# ps.net
KiCad netlist of a schematic drawn in Altium Designer
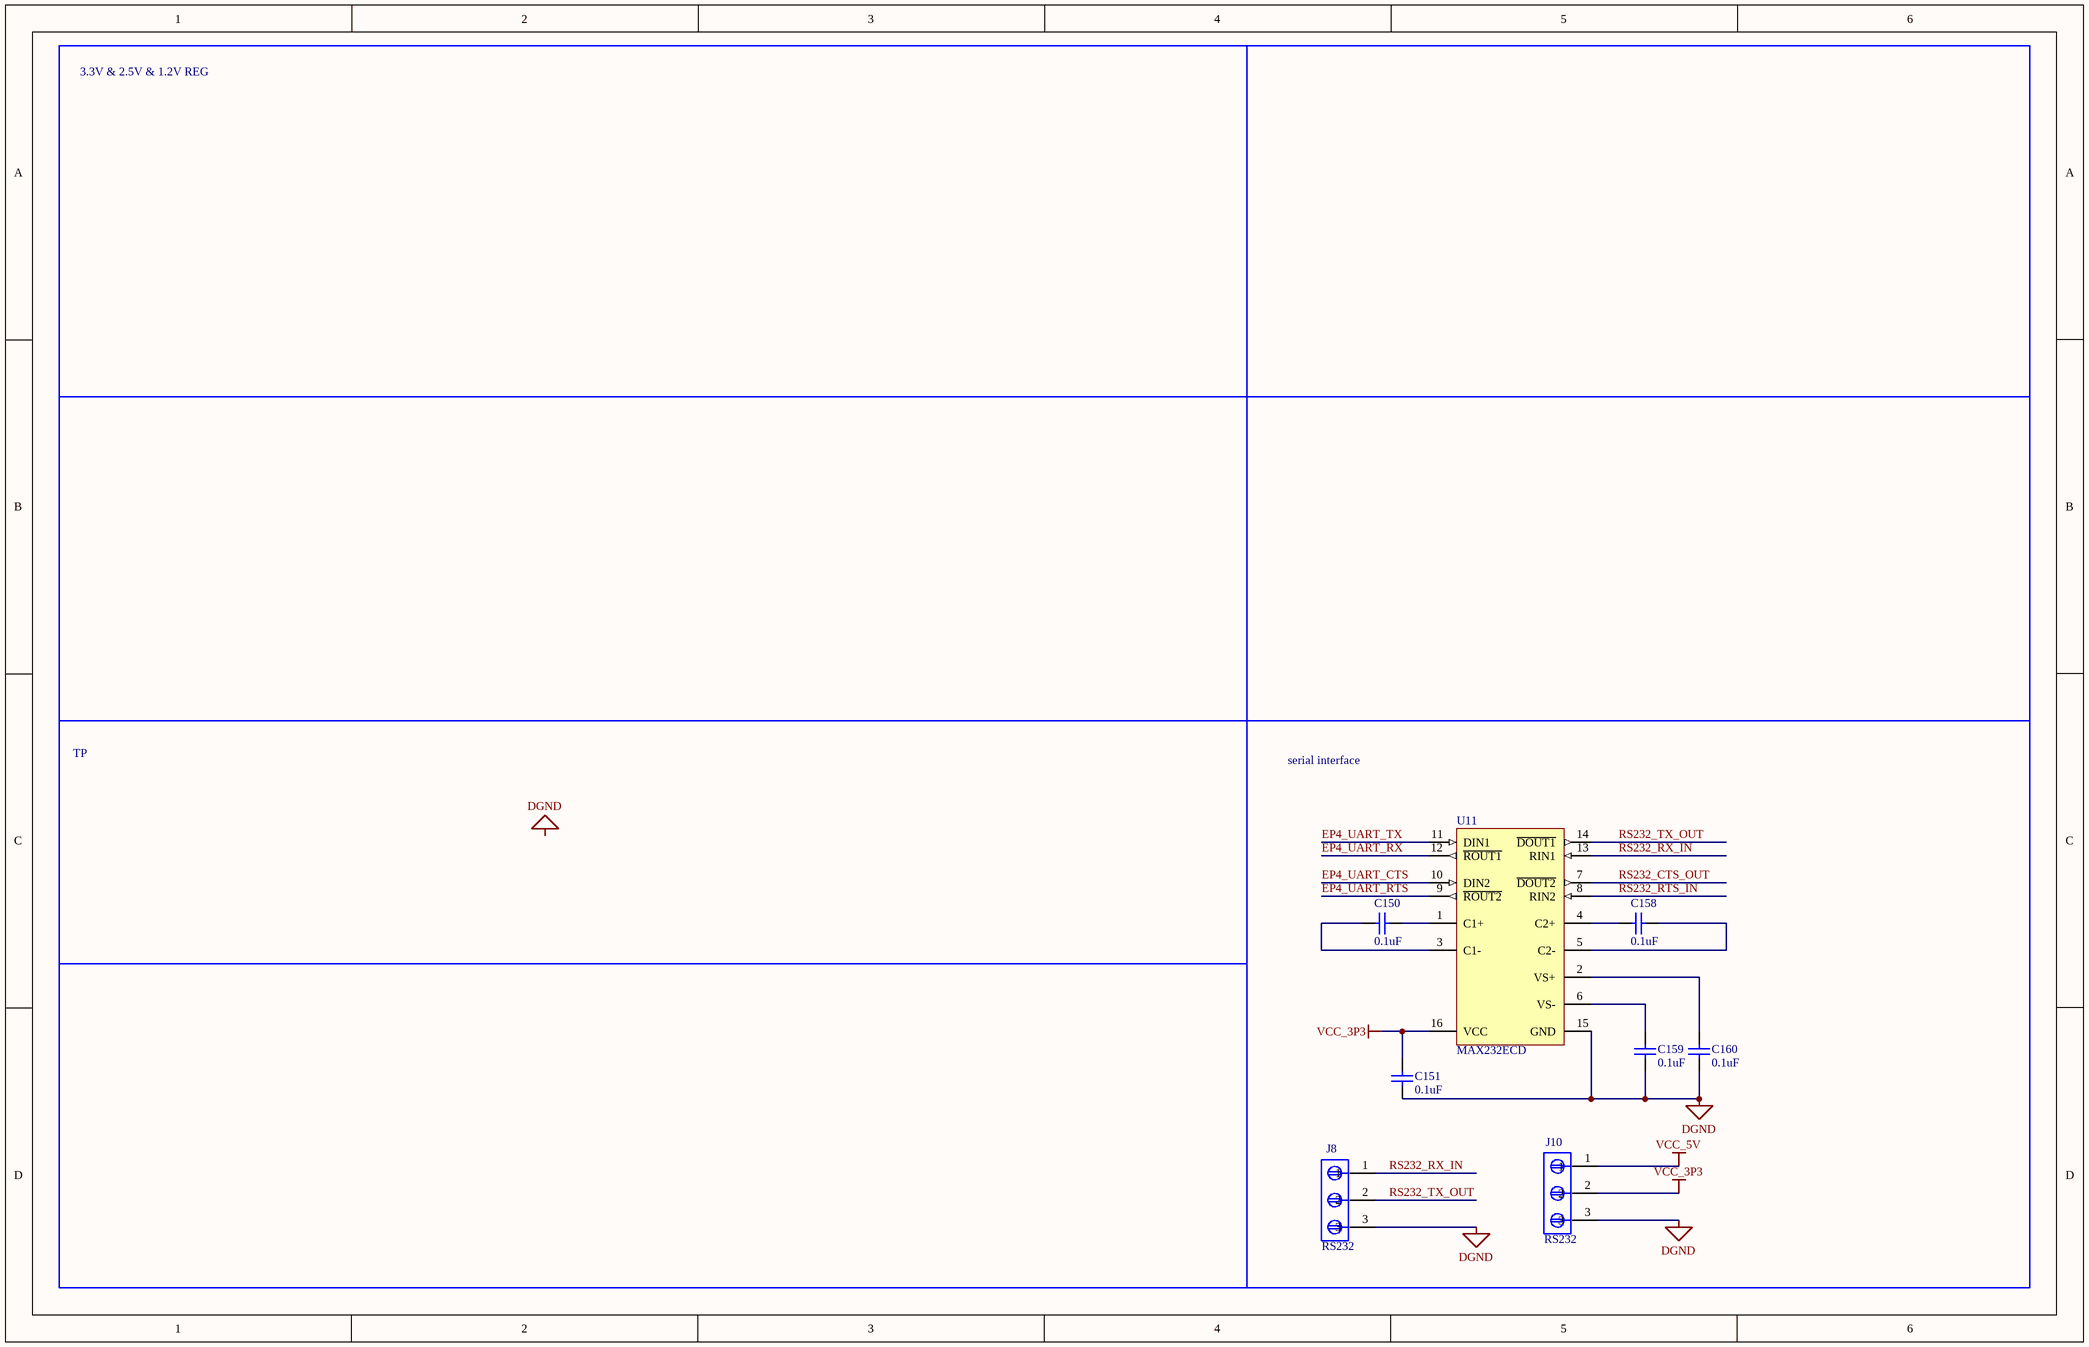
[diagram p0: ps.SchDoc]

(export (version "E")
  (design (tool "Eeschema 10.0.6"))
  (components
    (comp (ref "C150")
      (value "0.1uF")
      (footprint "C_0402")
      (description "Capacitor (Semiconductor SIM Model)")
      (fields (field (name "Comment") "Capacitor") (field (name "PUBLISHER") "Altium Limited"))
      (libsource (lib "Miscellaneous Devices") (part "Cap Semi"))
    )
    (comp (ref "C151")
      (value "0.1uF")
      (footprint "C_0402")
      (description "Capacitor (Semiconductor SIM Model)")
      (fields (field (name "Comment") "Capacitor") (field (name "PUBLISHER") "Altium Limited"))
      (libsource (lib "Miscellaneous Devices") (part "Cap Semi"))
    )
    (comp (ref "C158")
      (value "0.1uF")
      (footprint "C_0402")
      (description "Capacitor (Semiconductor SIM Model)")
      (fields (field (name "Comment") "Capacitor") (field (name "PUBLISHER") "Altium Limited"))
      (libsource (lib "Miscellaneous Devices") (part "Cap Semi"))
    )
    (comp (ref "C159")
      (value "0.1uF")
      (footprint "C_0402")
      (description "Capacitor (Semiconductor SIM Model)")
      (fields (field (name "Comment") "Capacitor") (field (name "PUBLISHER") "Altium Limited"))
      (libsource (lib "Miscellaneous Devices") (part "Cap Semi"))
    )
    (comp (ref "C160")
      (value "0.1uF")
      (footprint "C_0402")
      (description "Capacitor (Semiconductor SIM Model)")
      (fields (field (name "Comment") "Capacitor") (field (name "PUBLISHER") "Altium Limited"))
      (libsource (lib "Miscellaneous Devices") (part "Cap Semi"))
    )
    (comp (ref "J8")
      (value "RS232")
      (footprint "CON3-2.54")
      (fields (field (name "Comment") "DF3A-3P"))
      (libsource (lib "PCB_Project_1") (part "TERMDF3A-3P"))
    )
    (comp (ref "J10")
      (value "RS232")
      (footprint "CON3-2.54")
      (fields (field (name "Comment") "DF3A-3P"))
      (libsource (lib "PCB_Project_1") (part "TERMDF3A-3P"))
    )
    (comp (ref "U11")
      (value "MAX232ECD")
      (footprint "TI-D16_N")
      (libsource (lib "Texas Instruments Interface RS-232") (part "MAX232ECD"))
    )
  )
  (nets
    (net (code "1") (name "/EP4_UART_CTS") (class "Default")
      (node (ref "U11") (pin "10") (pinfunction "DIN2_10") (pintype "input"))
    )
    (net (code "2") (name "/EP4_UART_RTS") (class "Default")
      (node (ref "U11") (pin "9") (pinfunction "~{ROUT2}_9") (pintype "output"))
    )
    (net (code "3") (name "/EP4_UART_RX") (class "Default")
      (node (ref "U11") (pin "12") (pinfunction "~{ROUT1}_12") (pintype "output"))
    )
    (net (code "4") (name "/EP4_UART_TX") (class "Default")
      (node (ref "U11") (pin "11") (pinfunction "DIN1_11") (pintype "input"))
    )
    (net (code "5") (name "/RS232_CTS_OUT") (class "Default")
      (node (ref "U11") (pin "7") (pinfunction "~{DOUT2}_7") (pintype "output"))
    )
    (net (code "6") (name "/RS232_RTS_IN") (class "Default")
      (node (ref "U11") (pin "8") (pinfunction "RIN2_8") (pintype "input"))
    )
    (net (code "7") (name "/RS232_RX_IN") (class "Default")
      (node (ref "J8") (pin "1") (pinfunction "1_1") (pintype "passive"))
      (node (ref "U11") (pin "13") (pinfunction "RIN1_13") (pintype "input"))
    )
    (net (code "8") (name "/RS232_TX_OUT") (class "Default")
      (node (ref "J8") (pin "2") (pinfunction "2_2") (pintype "passive"))
      (node (ref "U11") (pin "14") (pinfunction "~{DOUT1}_14") (pintype "output"))
    )
    (net (code "9") (name "DGND") (class "Default")
      (node (ref "C151") (pin "2") (pinfunction "2_2") (pintype "passive"))
      (node (ref "C159") (pin "1") (pinfunction "1_1") (pintype "passive"))
      (node (ref "C160") (pin "2") (pinfunction "2_2") (pintype "passive"))
      (node (ref "J10") (pin "3") (pinfunction "3_3") (pintype "passive"))
      (node (ref "J8") (pin "3") (pinfunction "3_3") (pintype "passive"))
      (node (ref "U11") (pin "15") (pinfunction "GND_15") (pintype "power_in"))
    )
    (net (code "10") (name "Net-(U11-C1+)") (class "Default")
      (node (ref "C150") (pin "2") (pinfunction "2_2") (pintype "passive"))
      (node (ref "U11") (pin "1") (pinfunction "C1+_1") (pintype "passive"))
    )
    (net (code "11") (name "Net-(U11-C1-)") (class "Default")
      (node (ref "C150") (pin "1") (pinfunction "1_1") (pintype "passive"))
      (node (ref "U11") (pin "3") (pinfunction "C1-_3") (pintype "passive"))
    )
    (net (code "12") (name "Net-(U11-C2+)") (class "Default")
      (node (ref "C158") (pin "2") (pinfunction "2_2") (pintype "passive"))
      (node (ref "U11") (pin "4") (pinfunction "C2+_4") (pintype "passive"))
    )
    (net (code "13") (name "Net-(U11-C2-)") (class "Default")
      (node (ref "C158") (pin "1") (pinfunction "1_1") (pintype "passive"))
      (node (ref "U11") (pin "5") (pinfunction "C2-_5") (pintype "passive"))
    )
    (net (code "14") (name "Net-(U11-VS+)") (class "Default")
      (node (ref "C160") (pin "1") (pinfunction "1_1") (pintype "passive"))
      (node (ref "U11") (pin "2") (pinfunction "VS+_2") (pintype "power_in"))
    )
    (net (code "15") (name "Net-(U11-VS-)") (class "Default")
      (node (ref "C159") (pin "2") (pinfunction "2_2") (pintype "passive"))
      (node (ref "U11") (pin "6") (pinfunction "VS-_6") (pintype "power_in"))
    )
    (net (code "16") (name "VCC_3P3") (class "Default")
      (node (ref "C151") (pin "1") (pinfunction "1_1") (pintype "passive"))
      (node (ref "J10") (pin "2") (pinfunction "2_2") (pintype "passive"))
      (node (ref "U11") (pin "16") (pinfunction "VCC_16") (pintype "power_in"))
    )
    (net (code "17") (name "VCC_5V") (class "Default")
      (node (ref "J10") (pin "1") (pinfunction "1_1") (pintype "passive"))
    )
  )
)
